# p7_1_3v3.net
KiCad netlist of a schematic drawn in EAGLE
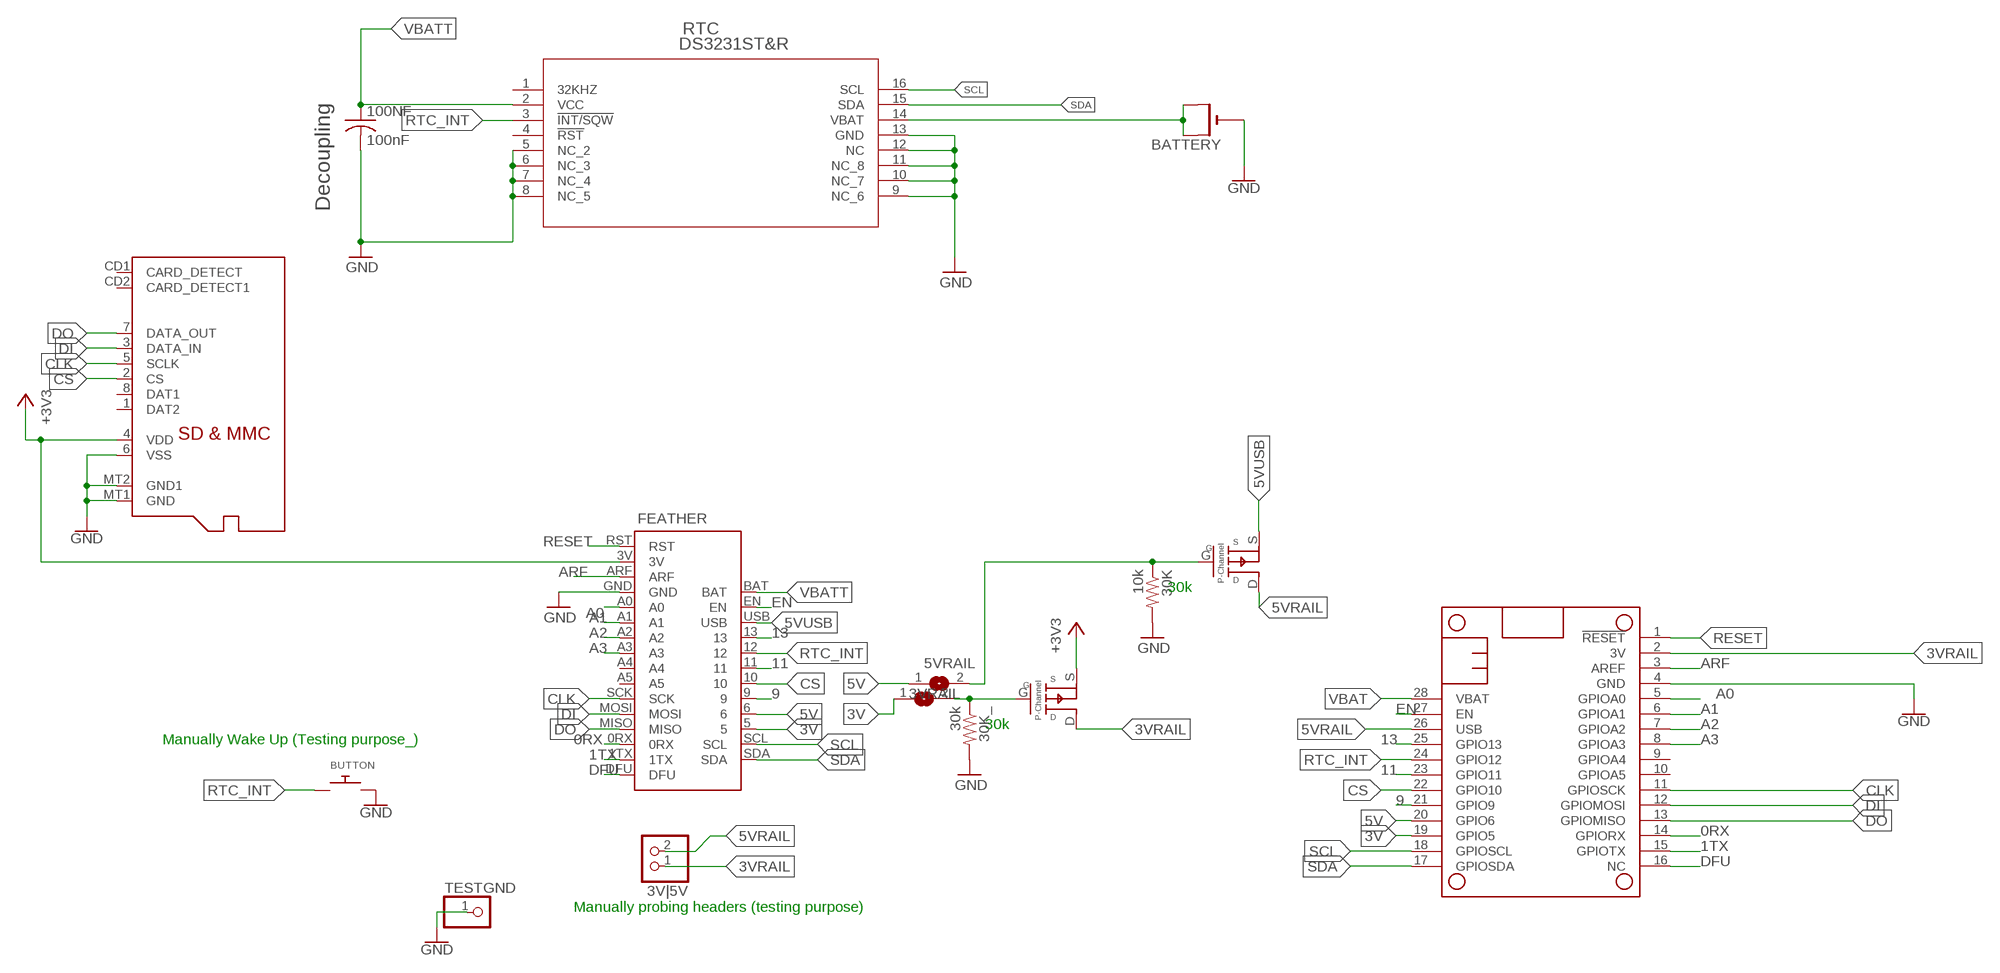
[diagram p0: schematic, sheet 1]

(export (version "E")
  (design (tool "Eeschema 10.0.6"))
  (components
    (comp (ref "3VRAIL")
      (value "SJ")
      (footprint "eagle-import:SJ")
      (libsource (lib "eagle-import") (part "SJ"))
    )
    (comp (ref "3V|5V")
      (value "PINHD-1X2")
      (footprint "eagle-import:1X02")
      (libsource (lib "eagle-import") (part "PINHD-1X2"))
    )
    (comp (ref "5VRAIL")
      (value "SJ")
      (footprint "eagle-import:SJ")
      (libsource (lib "eagle-import") (part "SJ"))
    )
    (comp (ref "30K")
      (value "10k")
      (footprint "eagle-import:R1206")
      (libsource (lib "eagle-import") (part "R-US_R1206"))
    )
    (comp (ref "30K_")
      (value "30k")
      (footprint "eagle-import:R1206")
      (libsource (lib "eagle-import") (part "R-US_R1206"))
    )
    (comp (ref "100NF")
      (value "100nF")
      (footprint "eagle-import:C1206")
      (libsource (lib "eagle-import") (part "C-USC1206"))
    )
    (comp (ref "BATTERY")
      (value "CR1220SMT")
      (footprint "eagle-import:CR1220-SMD")
      (libsource (lib "eagle-import") (part "CR1220SMT"))
    )
    (comp (ref "BUTTON")
      (value "SWITCH_PUSHBUTTONSOFTTOUCHSMD_SJ")
      (footprint "eagle-import:PUSHBUTTON_SMD_SJ")
      (libsource (lib "eagle-import") (part "SWITCH_PUSHBUTTONSOFTTOUCHSMD_SJ"))
    )
    (comp (ref "FEATHER")
      (value "BLUEFRUIT_M0")
      (footprint "eagle-import:BLUEFRUIT_MO")
      (libsource (lib "eagle-import") (part "BLUEFRUIT_M0"))
    )
    (comp (ref "MICROSD")
      (value "MICROSD")
      (footprint "eagle-import:MICROSD")
      (libsource (lib "eagle-import") (part "MICROSD"))
    )
    (comp (ref "MS1")
      (value "FEATHERWING")
      (footprint "eagle-import:FEATHERWING")
      (libsource (lib "eagle-import") (part "FEATHERWING"))
    )
    (comp (ref "PMOS")
      (value "SSM3J3228R")
      (footprint "eagle-import:SOT-23-3")
      (libsource (lib "eagle-import") (part "SSM3J3228R"))
    )
    (comp (ref "PMOS_")
      (value "SSM3J3228R")
      (footprint "eagle-import:SOT-23-3")
      (libsource (lib "eagle-import") (part "SSM3J3228R"))
    )
    (comp (ref "RTC")
      (value "DS3231ST&R")
      (footprint "eagle-import:21-0042B_16")
      (fields (field (name "MANUFACTURER_PART_NUMBER") "DS3231S#T&R"))
      (libsource (lib "eagle-import") (part "DS3231ST&R"))
    )
    (comp (ref "TESTGND")
      (value "PINHD-1X1")
      (footprint "eagle-import:1X01")
      (libsource (lib "eagle-import") (part "PINHD-1X1"))
    )
  )
  (nets
    (net (code "1") (name "+3V3") (class "Default")
      (node (ref "FEATHER") (pin "3V") (pinfunction "3V_3V") (pintype "bidirectional"))
      (node (ref "MICROSD") (pin "4") (pinfunction "VDD_4") (pintype "power_in"))
      (node (ref "PMOS") (pin "S") (pinfunction "S_S") (pintype "bidirectional"))
    )
    (net (code "2") (name "/0RX") (class "Default")
      (node (ref "FEATHER") (pin "0RX") (pinfunction "0RX_0RX") (pintype "bidirectional"))
      (node (ref "MS1") (pin "14") (pinfunction "GPIORX_14") (pintype "bidirectional"))
    )
    (net (code "3") (name "/1TX") (class "Default")
      (node (ref "FEATHER") (pin "1TX") (pinfunction "1TX_1TX") (pintype "bidirectional"))
      (node (ref "MS1") (pin "15") (pinfunction "GPIOTX_15") (pintype "bidirectional"))
    )
    (net (code "4") (name "/9") (class "Default")
      (node (ref "FEATHER") (pin "9") (pinfunction "9_9") (pintype "bidirectional"))
      (node (ref "MS1") (pin "21") (pinfunction "GPIO9_21") (pintype "bidirectional"))
    )
    (net (code "5") (name "/11") (class "Default")
      (node (ref "FEATHER") (pin "11") (pinfunction "11_11") (pintype "bidirectional"))
      (node (ref "MS1") (pin "23") (pinfunction "GPIO11_23") (pintype "bidirectional"))
    )
    (net (code "6") (name "/13") (class "Default")
      (node (ref "FEATHER") (pin "13") (pinfunction "13_13") (pintype "bidirectional"))
      (node (ref "MS1") (pin "25") (pinfunction "GPIO13_25") (pintype "bidirectional"))
    )
    (net (code "7") (name "/A0") (class "Default")
      (node (ref "FEATHER") (pin "A0") (pinfunction "A0_A0") (pintype "bidirectional"))
      (node (ref "MS1") (pin "5") (pinfunction "GPIOA0_5") (pintype "bidirectional"))
    )
    (net (code "8") (name "/A1") (class "Default")
      (node (ref "FEATHER") (pin "A1") (pinfunction "A1_A1") (pintype "bidirectional"))
      (node (ref "MS1") (pin "6") (pinfunction "GPIOA1_6") (pintype "bidirectional"))
    )
    (net (code "9") (name "/A2") (class "Default")
      (node (ref "FEATHER") (pin "A2") (pinfunction "A2_A2") (pintype "bidirectional"))
      (node (ref "MS1") (pin "7") (pinfunction "GPIOA2_7") (pintype "bidirectional"))
    )
    (net (code "10") (name "/A3") (class "Default")
      (node (ref "FEATHER") (pin "A3") (pinfunction "A3_A3") (pintype "bidirectional"))
      (node (ref "MS1") (pin "8") (pinfunction "GPIOA3_8") (pintype "bidirectional"))
    )
    (net (code "11") (name "/ARF") (class "Default")
      (node (ref "FEATHER") (pin "ARF") (pinfunction "ARF_ARF") (pintype "bidirectional"))
      (node (ref "MS1") (pin "3") (pinfunction "AREF_3") (pintype "passive"))
    )
    (net (code "12") (name "/DFU") (class "Default")
      (node (ref "FEATHER") (pin "DFU") (pinfunction "DFU_DFU") (pintype "bidirectional"))
      (node (ref "MS1") (pin "16") (pinfunction "NC_16") (pintype "passive"))
    )
    (net (code "13") (name "/EN") (class "Default")
      (node (ref "FEATHER") (pin "EN") (pinfunction "EN_EN") (pintype "bidirectional"))
      (node (ref "MS1") (pin "27") (pinfunction "EN_27") (pintype "passive"))
    )
    (net (code "14") (name "3V") (class "Default")
      (node (ref "3VRAIL") (pin "1") (pinfunction "1_1") (pintype "passive"))
      (node (ref "FEATHER") (pin "5") (pinfunction "5_5") (pintype "bidirectional"))
      (node (ref "MS1") (pin "19") (pinfunction "GPIO5_19") (pintype "bidirectional"))
    )
    (net (code "15") (name "3VRAIL") (class "Default")
      (node (ref "3V|5V") (pin "1") (pinfunction "1_1") (pintype "passive"))
      (node (ref "MS1") (pin "2") (pinfunction "3V_2") (pintype "power_in"))
      (node (ref "PMOS") (pin "D") (pinfunction "D_D") (pintype "bidirectional"))
    )
    (net (code "16") (name "5V") (class "Default")
      (node (ref "5VRAIL") (pin "1") (pinfunction "1_1") (pintype "passive"))
      (node (ref "FEATHER") (pin "6") (pinfunction "6_6") (pintype "bidirectional"))
      (node (ref "MS1") (pin "20") (pinfunction "GPIO6_20") (pintype "bidirectional"))
    )
    (net (code "17") (name "5VRAIL") (class "Default")
      (node (ref "30K") (pin "1") (pinfunction "1_1") (pintype "passive"))
      (node (ref "3V|5V") (pin "2") (pinfunction "2_2") (pintype "passive"))
      (node (ref "5VRAIL") (pin "2") (pinfunction "2_2") (pintype "passive"))
      (node (ref "MS1") (pin "26") (pinfunction "USB_26") (pintype "power_in"))
      (node (ref "PMOS_") (pin "D") (pinfunction "D_D") (pintype "bidirectional"))
      (node (ref "PMOS_") (pin "G") (pinfunction "G_G") (pintype "bidirectional"))
    )
    (net (code "18") (name "5VUSB") (class "Default")
      (node (ref "FEATHER") (pin "USB") (pinfunction "USB_USB") (pintype "bidirectional"))
      (node (ref "PMOS_") (pin "S") (pinfunction "S_S") (pintype "bidirectional"))
    )
    (net (code "19") (name "CLK") (class "Default")
      (node (ref "FEATHER") (pin "SCK") (pinfunction "SCK_SCK") (pintype "bidirectional"))
      (node (ref "MICROSD") (pin "5") (pinfunction "SCLK_5") (pintype "input"))
      (node (ref "MS1") (pin "11") (pinfunction "GPIOSCK_11") (pintype "bidirectional"))
    )
    (net (code "20") (name "CS") (class "Default")
      (node (ref "FEATHER") (pin "10") (pinfunction "10_10") (pintype "bidirectional"))
      (node (ref "MICROSD") (pin "2") (pinfunction "CS_2") (pintype "input"))
      (node (ref "MS1") (pin "22") (pinfunction "GPIO10_22") (pintype "bidirectional"))
    )
    (net (code "21") (name "DI") (class "Default")
      (node (ref "FEATHER") (pin "MOSI") (pinfunction "MOSI_MOSI") (pintype "bidirectional"))
      (node (ref "MICROSD") (pin "3") (pinfunction "DATA_IN_3") (pintype "input"))
      (node (ref "MS1") (pin "12") (pinfunction "GPIOMOSI_12") (pintype "bidirectional"))
    )
    (net (code "22") (name "DO") (class "Default")
      (node (ref "FEATHER") (pin "MISO") (pinfunction "MISO_MISO") (pintype "bidirectional"))
      (node (ref "MICROSD") (pin "7") (pinfunction "DATA_OUT_7") (pintype "output"))
      (node (ref "MS1") (pin "13") (pinfunction "GPIOMISO_13") (pintype "bidirectional"))
    )
    (net (code "23") (name "GND") (class "Default")
      (node (ref "100NF") (pin "2") (pinfunction "2_2") (pintype "passive"))
      (node (ref "30K") (pin "2") (pinfunction "2_2") (pintype "passive"))
      (node (ref "30K_") (pin "2") (pinfunction "2_2") (pintype "passive"))
      (node (ref "BATTERY") (pin "-") (pinfunction "-_-") (pintype "passive"))
      (node (ref "BUTTON") (pin "P$2") (pinfunction "P$2_P$2") (pintype "passive"))
      (node (ref "FEATHER") (pin "GND") (pinfunction "GND_GND") (pintype "bidirectional"))
      (node (ref "MICROSD") (pin "6") (pinfunction "VSS_6") (pintype "power_in"))
      (node (ref "MICROSD") (pin "MT1") (pinfunction "GND_MT1") (pintype "power_in"))
      (node (ref "MICROSD") (pin "MT2") (pinfunction "GND1_MT2") (pintype "power_in"))
      (node (ref "MS1") (pin "4") (pinfunction "GND_4") (pintype "power_in"))
      (node (ref "RTC") (pin "10") (pinfunction "NC_7_10") (pintype "passive"))
      (node (ref "RTC") (pin "11") (pinfunction "NC_8_11") (pintype "passive"))
      (node (ref "RTC") (pin "12") (pinfunction "NC_12") (pintype "passive"))
      (node (ref "RTC") (pin "13") (pinfunction "GND_13") (pintype "power_in"))
      (node (ref "RTC") (pin "5") (pinfunction "NC_2_5") (pintype "passive"))
      (node (ref "RTC") (pin "6") (pinfunction "NC_3_6") (pintype "passive"))
      (node (ref "RTC") (pin "7") (pinfunction "NC_4_7") (pintype "passive"))
      (node (ref "RTC") (pin "8") (pinfunction "NC_5_8") (pintype "passive"))
      (node (ref "RTC") (pin "9") (pinfunction "NC_6_9") (pintype "passive"))
      (node (ref "TESTGND") (pin "1") (pinfunction "1_1") (pintype "passive"))
    )
    (net (code "24") (name "Net-(30K_-Pad1)") (class "Default")
      (node (ref "30K_") (pin "1") (pinfunction "1_1") (pintype "passive"))
      (node (ref "3VRAIL") (pin "2") (pinfunction "2_2") (pintype "passive"))
      (node (ref "PMOS") (pin "G") (pinfunction "G_G") (pintype "bidirectional"))
    )
    (net (code "25") (name "Net-(BATTERY-+)") (class "Default")
      (node (ref "BATTERY") (pin "+$1") (pinfunction "+_+$1") (pintype "passive"))
      (node (ref "BATTERY") (pin "+$2") (pinfunction "+1_+$2") (pintype "passive"))
      (node (ref "RTC") (pin "14") (pinfunction "VBAT_14") (pintype "power_in"))
    )
    (net (code "26") (name "RESET") (class "Default")
      (node (ref "FEATHER") (pin "RST") (pinfunction "RST_RST") (pintype "bidirectional"))
      (node (ref "MS1") (pin "1") (pinfunction "~{RESET}_1") (pintype "input"))
    )
    (net (code "27") (name "RTC_INT") (class "Default")
      (node (ref "BUTTON") (pin "P$1") (pinfunction "P$1_P$1") (pintype "passive"))
      (node (ref "FEATHER") (pin "12") (pinfunction "12_12") (pintype "bidirectional"))
      (node (ref "MS1") (pin "24") (pinfunction "GPIO12_24") (pintype "bidirectional"))
      (node (ref "RTC") (pin "3") (pinfunction "~{INT/SQW}_3") (pintype "passive"))
    )
    (net (code "28") (name "SCL") (class "Default")
      (node (ref "FEATHER") (pin "SCL") (pinfunction "SCL_SCL") (pintype "bidirectional"))
      (node (ref "MS1") (pin "18") (pinfunction "GPIOSCL_18") (pintype "bidirectional"))
      (node (ref "RTC") (pin "16") (pinfunction "SCL_16") (pintype "passive"))
    )
    (net (code "29") (name "SDA") (class "Default")
      (node (ref "FEATHER") (pin "SDA") (pinfunction "SDA_SDA") (pintype "bidirectional"))
      (node (ref "MS1") (pin "17") (pinfunction "GPIOSDA_17") (pintype "bidirectional"))
      (node (ref "RTC") (pin "15") (pinfunction "SDA_15") (pintype "passive"))
    )
    (net (code "30") (name "VBAT") (class "Default")
      (node (ref "MS1") (pin "28") (pinfunction "VBAT_28") (pintype "power_in"))
    )
    (net (code "31") (name "VBATT") (class "Default")
      (node (ref "100NF") (pin "1") (pinfunction "1_1") (pintype "passive"))
      (node (ref "FEATHER") (pin "BAT") (pinfunction "BAT_BAT") (pintype "bidirectional"))
      (node (ref "RTC") (pin "2") (pinfunction "VCC_2") (pintype "power_in"))
    )
    (net (code "32") (name "unconnected-(FEATHER-PadA4)") (class "Default")
      (node (ref "FEATHER") (pin "A4") (pinfunction "A4_A4") (pintype "bidirectional"))
    )
    (net (code "33") (name "unconnected-(FEATHER-PadA5)") (class "Default")
      (node (ref "FEATHER") (pin "A5") (pinfunction "A5_A5") (pintype "bidirectional"))
    )
    (net (code "34") (name "unconnected-(MICROSD-CARD_DETECT-PadCD1)") (class "Default")
      (node (ref "MICROSD") (pin "CD1") (pinfunction "CARD_DETECT_CD1") (pintype "passive"))
    )
    (net (code "35") (name "unconnected-(MICROSD-CARD_DETECT1-PadCD2)") (class "Default")
      (node (ref "MICROSD") (pin "CD2") (pinfunction "CARD_DETECT1_CD2") (pintype "passive"))
    )
    (net (code "36") (name "unconnected-(MICROSD-DAT1-Pad8)") (class "Default")
      (node (ref "MICROSD") (pin "8") (pinfunction "DAT1_8") (pintype "bidirectional"))
    )
    (net (code "37") (name "unconnected-(MICROSD-DAT2-Pad1)") (class "Default")
      (node (ref "MICROSD") (pin "1") (pinfunction "DAT2_1") (pintype "bidirectional"))
    )
    (net (code "38") (name "unconnected-(MS1-GPIOA4-Pad9)") (class "Default")
      (node (ref "MS1") (pin "9") (pinfunction "GPIOA4_9") (pintype "bidirectional"))
    )
    (net (code "39") (name "unconnected-(MS1-GPIOA5-Pad10)") (class "Default")
      (node (ref "MS1") (pin "10") (pinfunction "GPIOA5_10") (pintype "bidirectional"))
    )
    (net (code "40") (name "unconnected-(RTC-32KHZ-Pad1)") (class "Default")
      (node (ref "RTC") (pin "1") (pinfunction "32KHZ_1") (pintype "passive"))
    )
    (net (code "41") (name "unconnected-(RTC-~{RST}-Pad4)") (class "Default")
      (node (ref "RTC") (pin "4") (pinfunction "~{RST}_4") (pintype "passive"))
    )
  )
)
